# Power_Supply.net
KiCad netlist of a schematic drawn in Altium Designer
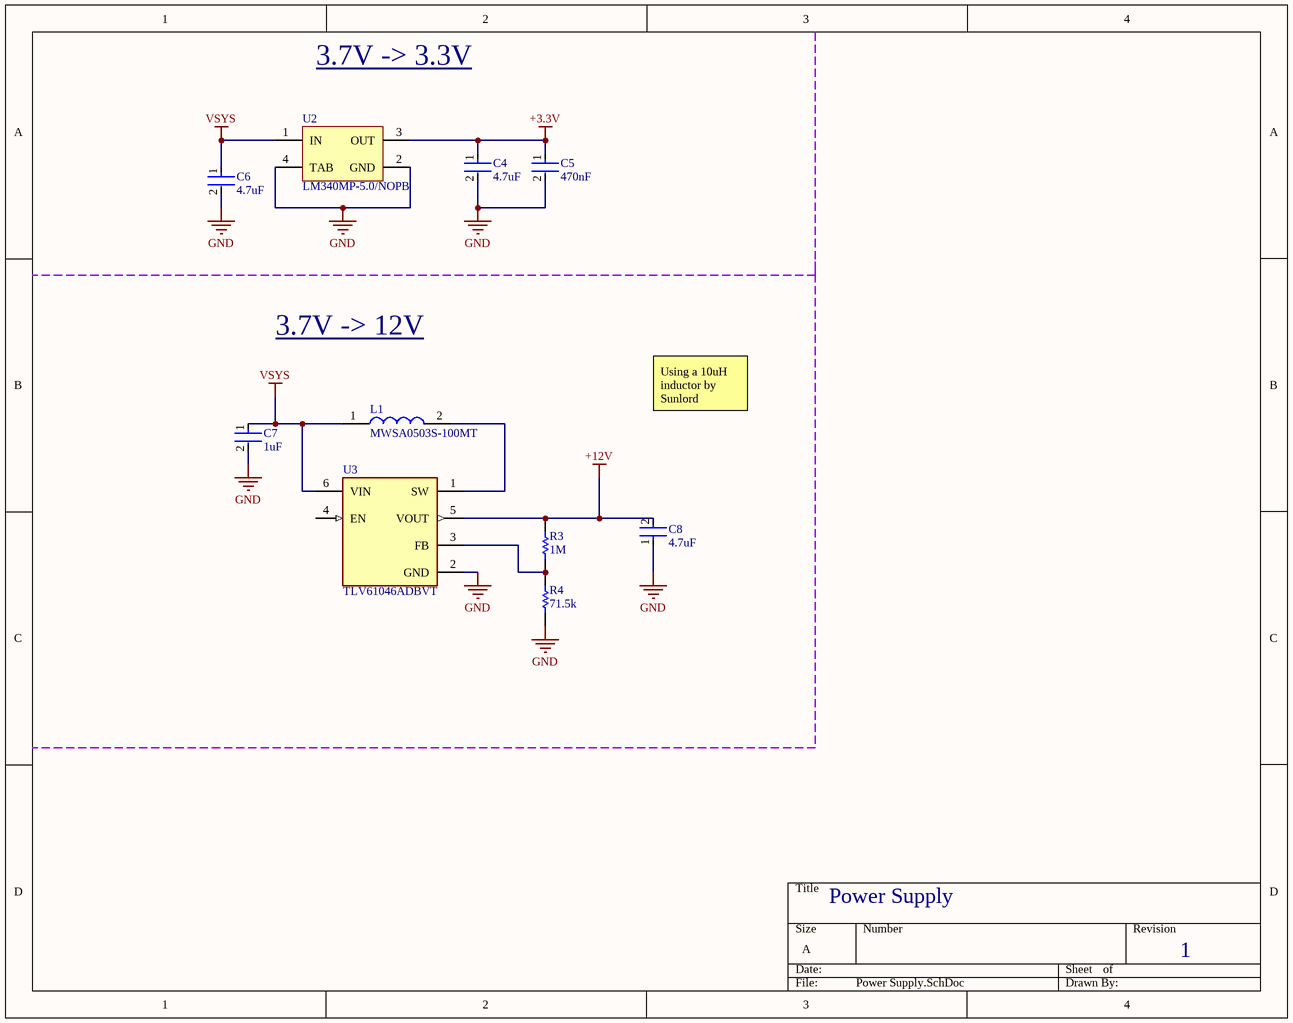
[diagram p0: Power Supply.SchDoc]

(export (version "E")
  (design (tool "Eeschema 10.0.6"))
  (components
    (comp (ref "C4")
      (value "4.7uF")
      (footprint "FP-CC0805-0_85-MFG")
      (description "CAP CER 0.1UF 50V X7R 0805")
      (fields (field (name "TOLERANCE") "0.1") (field (name "MANUFACTURER PART NUMBER") "CC0805KRX7R9BB104"))
      (libsource (lib "Altium Content Vault") (part "11868f565c42a9108669ba33697ecf6"))
    )
    (comp (ref "C5")
      (value "470nF")
      (footprint "FP-CC0805-0_85-MFG")
      (description "CAP CER 0.1UF 50V X7R 0805")
      (fields (field (name "TOLERANCE") "0.1") (field (name "MANUFACTURER PART NUMBER") "CC0805KRX7R9BB104"))
      (libsource (lib "Altium Content Vault") (part "11868f565c42a9108669ba33697ecf6"))
    )
    (comp (ref "C6")
      (value "4.7uF")
      (footprint "FP-CC0805-0_85-MFG")
      (description "CAP CER 0.1UF 50V X7R 0805")
      (fields (field (name "TOLERANCE") "0.1") (field (name "MANUFACTURER PART NUMBER") "CC0805KRX7R9BB104"))
      (libsource (lib "Altium Content Vault") (part "11868f565c42a9108669ba33697ecf6"))
    )
    (comp (ref "C7")
      (value "1uF")
      (footprint "FP-CC0805-0_85-MFG")
      (description "CAP CER 0.1UF 50V X7R 0805")
      (fields (field (name "TOLERANCE") "0.1") (field (name "MANUFACTURER PART NUMBER") "CC0805KRX7R9BB104"))
      (libsource (lib "Altium Content Vault") (part "11868f565c42a9108669ba33697ecf6"))
    )
    (comp (ref "C8")
      (value "4.7uF")
      (footprint "FP-CC0805-0_85-MFG")
      (description "CAP CER 0.1UF 50V X7R 0805")
      (fields (field (name "TOLERANCE") "0.1") (field (name "MANUFACTURER PART NUMBER") "CC0805KRX7R9BB104"))
      (libsource (lib "Altium Content Vault") (part "11868f565c42a9108669ba33697ecf6"))
    )
    (comp (ref "L1")
      (value "MWSA0503S-100MT")
      (footprint "SamacSys:MWSA0503S4R7MT")
      (fields (field (name "MANUFACTURER_PART_NUMBER") "MWSA0503S-4R7MT"))
      (libsource (lib "*") (part "MWSA0503S-4R7MT"))
    )
    (comp (ref "R3")
      (value "1M")
      (footprint "RESC2013X70X40ML20T20")
      (description "Chip Resistor, 1 KOhm, +/- 1%, 0.125 W, -55 to 155 degC, 0805 (2013 Metric)")
      (fields (field (name "POWER") "125mW") (field (name "TOLERANCE") "1%"))
      (libsource (lib "Formula Racing at UC Davis") (part "RES-2"))
    )
    (comp (ref "R4")
      (value "71.5k")
      (footprint "RESC2013X70X40ML20T20")
      (description "Chip Resistor, 1 KOhm, +/- 1%, 0.125 W, -55 to 155 degC, 0805 (2013 Metric)")
      (fields (field (name "POWER") "125mW") (field (name "TOLERANCE") "1%"))
      (libsource (lib "Formula Racing at UC Davis") (part "RES-2"))
    )
    (comp (ref "U2")
      (value "LM340MP-5.0/NOPB")
      (footprint "DCY0004A_L")
      (description "Series 3-Terminal Positive Regulators, 4-pin SOT-223, Pb-Free\r\nLCSC Part # C131990")
      (fields (field (name "MANUFACTURER") "Texas Instruments"))
      (libsource (lib "Altium Content Vault") (part "PM-REG-LM2940-TO4"))
    )
    (comp (ref "U3")
      (value "TLV61046ADBVT")
      (footprint "FP-DBV0006A-MFG")
      (description "IC REG BOOST ADJ SOT23-6\r\nWON'T BE POPULATED BY MANUFACTURER")
      (fields
        (field (name "OCTOPART") "https://octopart.com/tlv61046adbvt-texas+instruments-81856327")
        (field (name "MANUFACTURER") "Texas Instruments")
      )
      (libsource (lib "Altium Content Vault") (part "81c5d58341a3dd94edb5100ca13c041"))
    )
  )
  (nets
    (net (code "1") (name "+3.3V") (class "Default")
      (node (ref "C4") (pin "1") (pinfunction "1_1") (pintype "passive"))
      (node (ref "C5") (pin "1") (pinfunction "1_1") (pintype "passive"))
      (node (ref "U2") (pin "3") (pinfunction "OUT_3") (pintype "power_in"))
    )
    (net (code "2") (name "+12V") (class "Default")
      (node (ref "C8") (pin "2") (pinfunction "2_2") (pintype "passive"))
      (node (ref "R3") (pin "2") (pinfunction "2_2") (pintype "passive"))
      (node (ref "U3") (pin "5") (pinfunction "VOUT_5") (pintype "output"))
    )
    (net (code "3") (name "GND") (class "Default")
      (node (ref "C4") (pin "2") (pinfunction "2_2") (pintype "passive"))
      (node (ref "C5") (pin "2") (pinfunction "2_2") (pintype "passive"))
      (node (ref "C6") (pin "2") (pinfunction "2_2") (pintype "passive"))
      (node (ref "C7") (pin "2") (pinfunction "2_2") (pintype "passive"))
      (node (ref "C8") (pin "1") (pinfunction "1_1") (pintype "passive"))
      (node (ref "R4") (pin "1") (pinfunction "1_1") (pintype "passive"))
      (node (ref "U2") (pin "2") (pinfunction "GND_2") (pintype "power_in"))
      (node (ref "U2") (pin "4") (pinfunction "TAB_4") (pintype "power_in"))
      (node (ref "U3") (pin "2") (pinfunction "GND_2") (pintype "power_in"))
    )
    (net (code "4") (name "Net-(U3-FB)") (class "Default")
      (node (ref "R3") (pin "1") (pinfunction "1_1") (pintype "passive"))
      (node (ref "R4") (pin "2") (pinfunction "2_2") (pintype "passive"))
      (node (ref "U3") (pin "3") (pinfunction "FB_3") (pintype "passive"))
    )
    (net (code "5") (name "Net-(U3-SW)") (class "Default")
      (node (ref "L1") (pin "2") (pinfunction "2_2") (pintype "passive"))
      (node (ref "U3") (pin "1") (pinfunction "SW_1") (pintype "power_in"))
    )
    (net (code "6") (name "VSYS") (class "Default")
      (node (ref "C6") (pin "1") (pinfunction "1_1") (pintype "passive"))
      (node (ref "C7") (pin "1") (pinfunction "1_1") (pintype "passive"))
      (node (ref "L1") (pin "1") (pinfunction "1_1") (pintype "passive"))
      (node (ref "U2") (pin "1") (pinfunction "IN_1") (pintype "power_in"))
      (node (ref "U3") (pin "6") (pinfunction "VIN_6") (pintype "power_in"))
    )
    (net (code "7") (name "unconnected-(U3-EN-Pad4)") (class "Default")
      (node (ref "U3") (pin "4") (pinfunction "EN_4") (pintype "input"))
    )
  )
)
